# SCH-FlipperZero-FlipperPhone-V0_1.net
KiCad netlist of a schematic drawn in EasyEDA
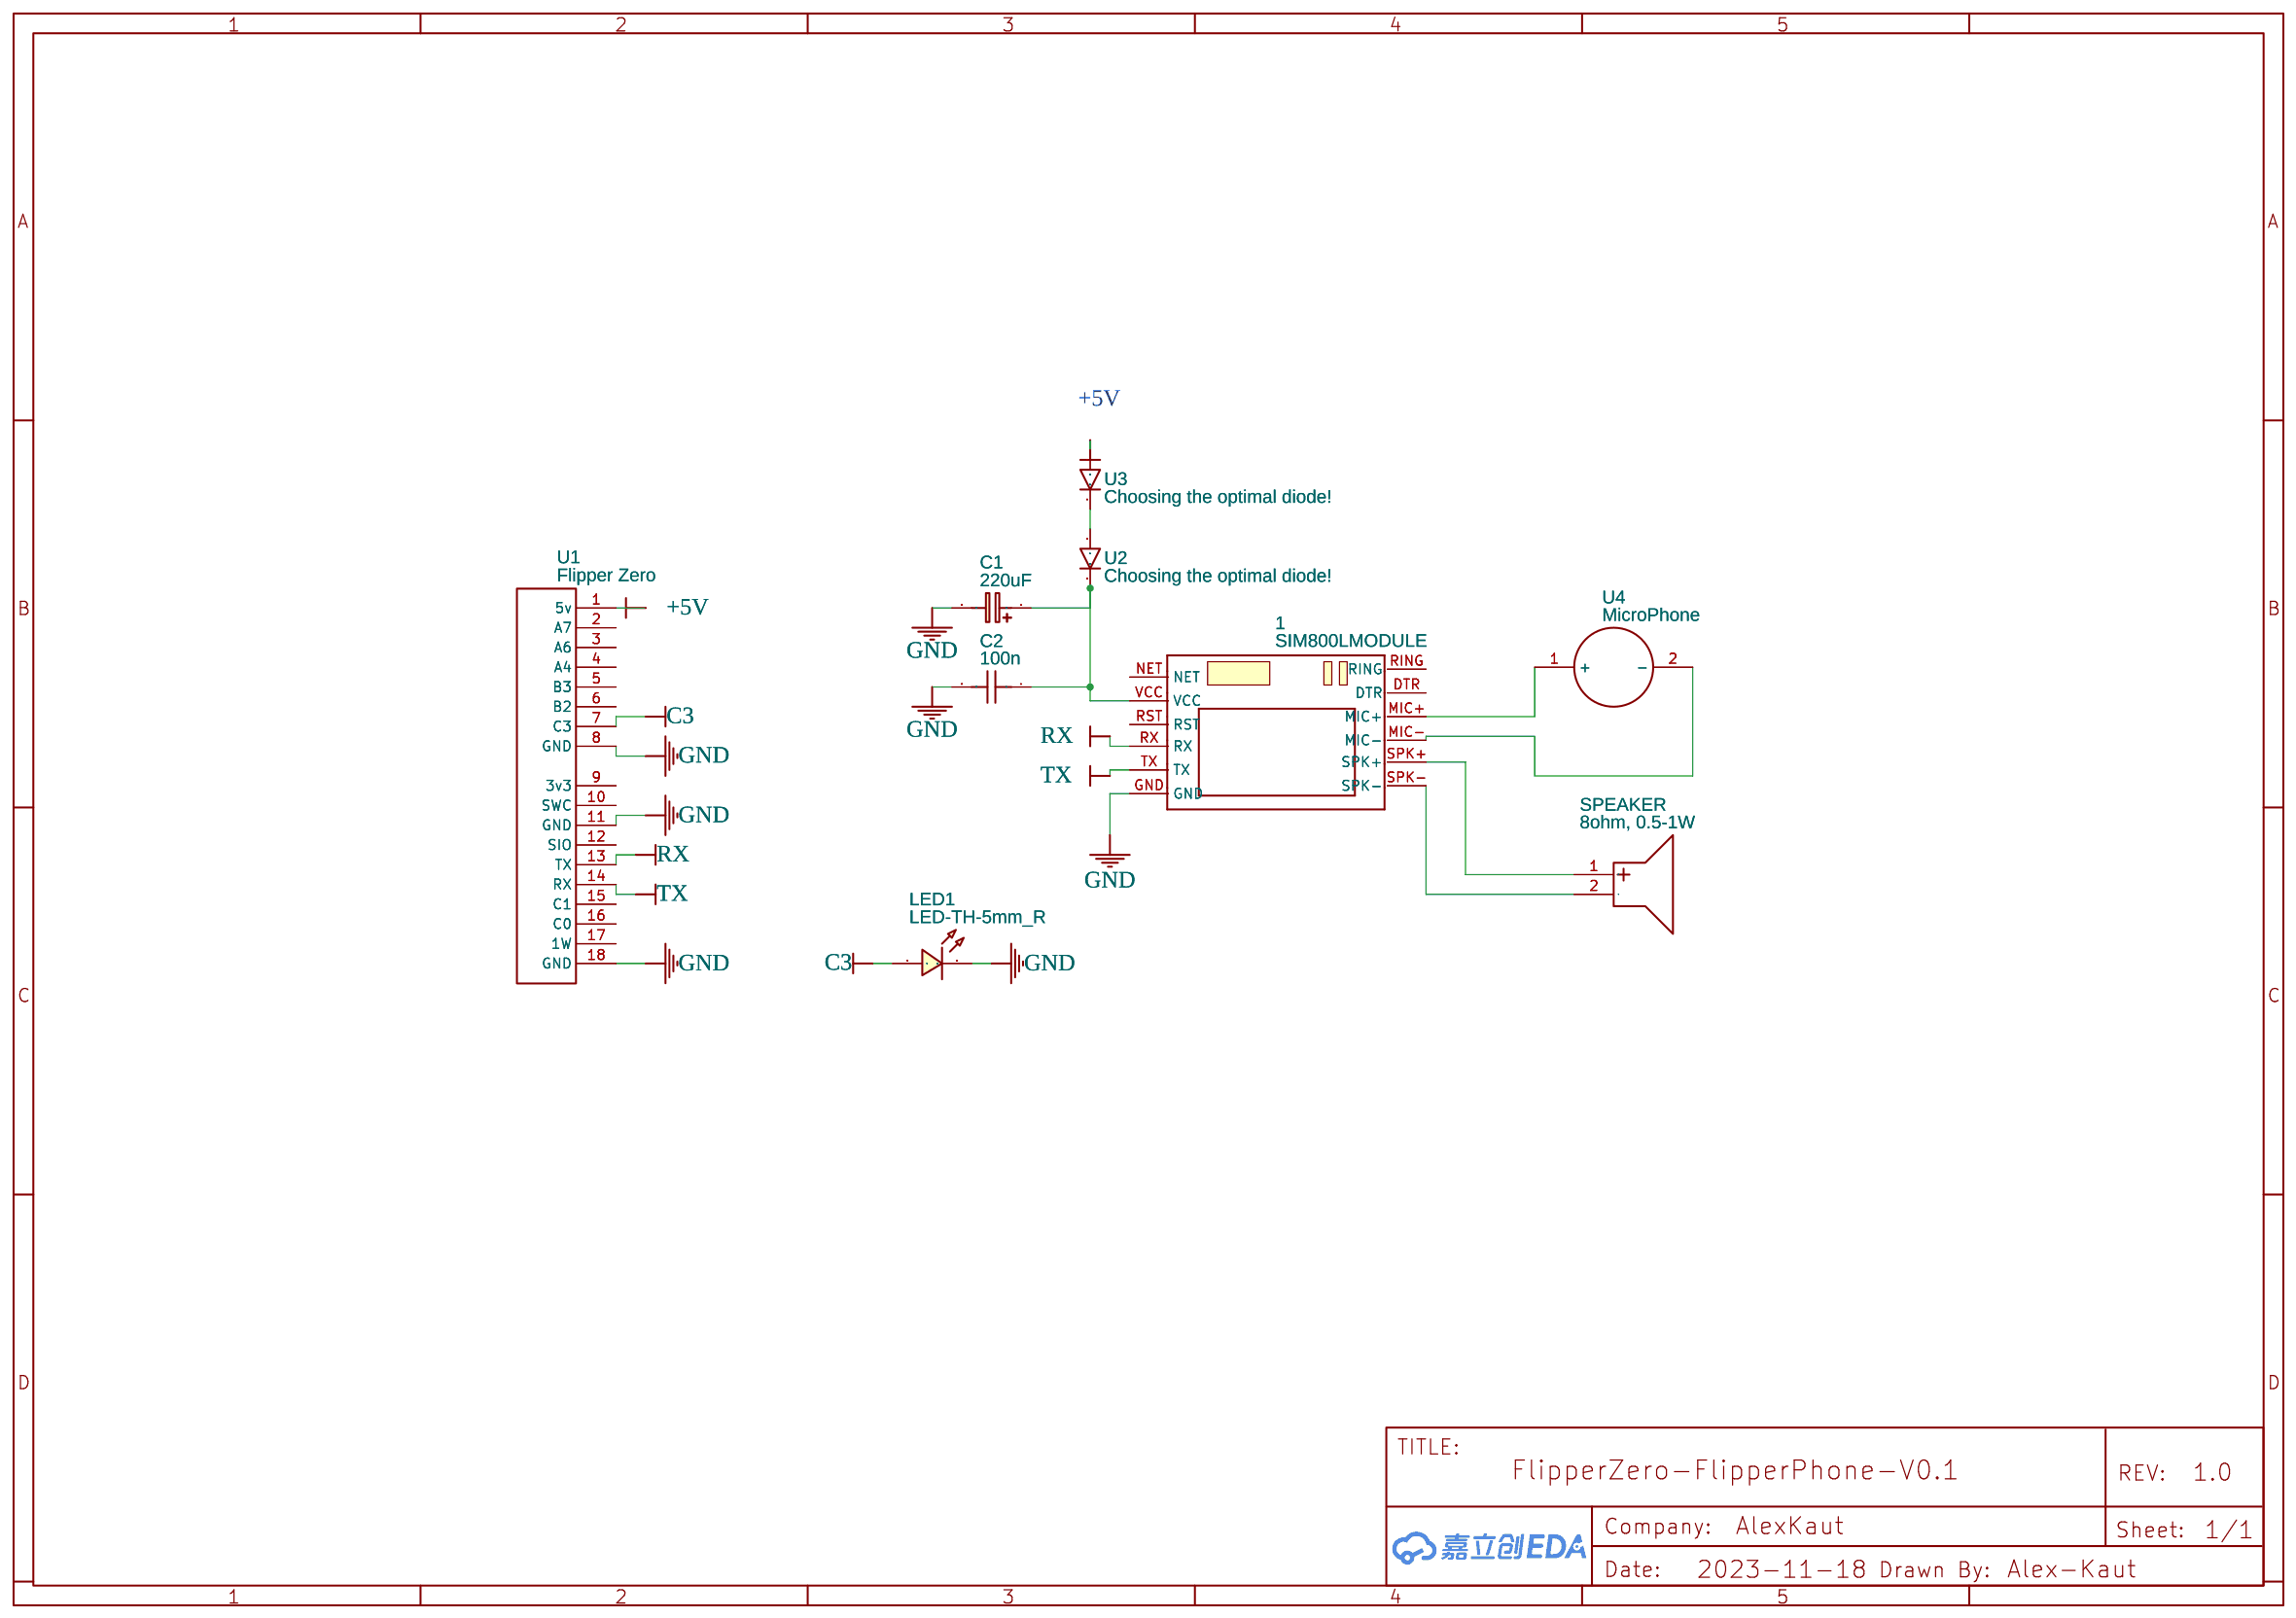
[diagram p0: schematic sheet]

(export (version "E")
  (design (tool "Eeschema 10.0.6"))
  (components
    (comp (ref "1") (value "SIM800LMODULE") (libsource (lib "") (part "SIM800LMODULE")))
    (comp (ref "C1") (value "220uF") (libsource (lib "") (part "CE_TH_D6.3×F2.5_EU")))
    (comp (ref "C2") (value "100n") (libsource (lib "") (part "C_RAD-0.2_US")))
    (comp (ref "LED1")
      (value "LED-TH-5mm_R")
      (fields
        (field (name "BOM_Manufacturer Part") "333-2SURD/S530-A3")
        (field (name "BOM_Supplier Part") "C87271")
      )
      (libsource (lib "") (part "LED-TH-5mm_R"))
    )
    (comp (ref "SPEAKER")
      (value "8ohm, 0.5-1W")
      (fields
        (field (name "BOM_Manufacturer Part") "BL-PBZ12065C2705YA")
        (field (name "BOM_Supplier Part") "C249440")
      )
      (libsource (lib "") (part "SPEAKER-30mm-8ohm-0.5w-TH"))
    )
    (comp (ref "U1") (value "Flipper Zero") (libsource (lib "") (part "Flipper Zero")))
    (comp (ref "U2") (value "Choosing the optimal diode!") (libsource (lib "") (part "1N4007A")))
    (comp (ref "U3") (value "Choosing the optimal diode!") (libsource (lib "") (part "1N4007A")))
    (comp (ref "U4") (value "MicroPhone") (libsource (lib "") (part "MicroPhone")))
  )
  (nets
    (net (code "1") (name "+5V") (class "Default")
      (node (ref "U1") (pin "1") (pinfunction "5v_1") (pintype "unspecified"))
      (node (ref "U3") (pin "1") (pinfunction "1_1") (pintype "unspecified"))
    )
    (net (code "2") (name "C3") (class "Default")
      (node (ref "LED1") (pin "1") (pinfunction "1_1") (pintype "unspecified"))
      (node (ref "U1") (pin "7") (pinfunction "C3_7") (pintype "unspecified"))
    )
    (net (code "3") (name "GND") (class "Default")
      (node (ref "1") (pin "GND") (pinfunction "GND_GND") (pintype "bidirectional"))
      (node (ref "C1") (pin "2") (pinfunction "2_2") (pintype "unspecified"))
      (node (ref "C2") (pin "2") (pinfunction "2_2") (pintype "unspecified"))
      (node (ref "LED1") (pin "2") (pinfunction "2_2") (pintype "unspecified"))
      (node (ref "U1") (pin "11") (pinfunction "GND_11") (pintype "unspecified"))
      (node (ref "U1") (pin "18") (pinfunction "GND_18") (pintype "unspecified"))
      (node (ref "U1") (pin "8") (pinfunction "GND_8") (pintype "unspecified"))
    )
    (net (code "4") (name "Net-(1-PadVCC)") (class "Default")
      (node (ref "1") (pin "VCC") (pinfunction "VCC_VCC") (pintype "bidirectional"))
      (node (ref "C1") (pin "1") (pinfunction "1_1") (pintype "unspecified"))
      (node (ref "C2") (pin "1") (pinfunction "1_1") (pintype "unspecified"))
      (node (ref "U2") (pin "2") (pinfunction "2_2") (pintype "unspecified"))
    )
    (net (code "5") (name "Net-(SPEAKER-+)") (class "Default")
      (node (ref "1") (pin "SPK+") (pinfunction "SPK+_SPK+") (pintype "bidirectional"))
      (node (ref "SPEAKER") (pin "1") (pinfunction "+_1") (pintype "unspecified"))
    )
    (net (code "6") (name "Net-(SPEAKER--)") (class "Default")
      (node (ref "1") (pin "SPK-") (pinfunction "SPK-_SPK-") (pintype "bidirectional"))
      (node (ref "SPEAKER") (pin "2") (pinfunction "-_2") (pintype "unspecified"))
    )
    (net (code "7") (name "Net-(U2-Pad1)") (class "Default")
      (node (ref "U2") (pin "1") (pinfunction "1_1") (pintype "unspecified"))
      (node (ref "U3") (pin "2") (pinfunction "2_2") (pintype "unspecified"))
    )
    (net (code "8") (name "Net-(U4-+)") (class "Default")
      (node (ref "1") (pin "MIC+") (pinfunction "MIC+_MIC+") (pintype "bidirectional"))
      (node (ref "U4") (pin "1") (pinfunction "+_1") (pintype "unspecified"))
    )
    (net (code "9") (name "Net-(U4--)") (class "Default")
      (node (ref "1") (pin "MIC-") (pinfunction "MIC-_MIC-") (pintype "bidirectional"))
      (node (ref "U4") (pin "2") (pinfunction "-_2") (pintype "unspecified"))
    )
    (net (code "10") (name "RX") (class "Default")
      (node (ref "1") (pin "RX") (pinfunction "RX_RX") (pintype "bidirectional"))
      (node (ref "U1") (pin "13") (pinfunction "TX_13") (pintype "unspecified"))
    )
    (net (code "11") (name "TX") (class "Default")
      (node (ref "1") (pin "TX") (pinfunction "TX_TX") (pintype "bidirectional"))
      (node (ref "U1") (pin "14") (pinfunction "RX_14") (pintype "unspecified"))
    )
    (net (code "12") (name "unconnected-(1-PadDTR)") (class "Default")
      (node (ref "1") (pin "DTR") (pinfunction "DTR_DTR") (pintype "bidirectional"))
    )
    (net (code "13") (name "unconnected-(1-PadNET)") (class "Default")
      (node (ref "1") (pin "NET") (pinfunction "NET_NET") (pintype "bidirectional"))
    )
    (net (code "14") (name "unconnected-(1-PadRING)") (class "Default")
      (node (ref "1") (pin "RING") (pinfunction "RING_RING") (pintype "bidirectional"))
    )
    (net (code "15") (name "unconnected-(1-PadRST)") (class "Default")
      (node (ref "1") (pin "RST") (pinfunction "RST_RST") (pintype "bidirectional"))
    )
    (net (code "16") (name "unconnected-(U1-1W-Pad17)") (class "Default")
      (node (ref "U1") (pin "17") (pinfunction "1W_17") (pintype "unspecified"))
    )
    (net (code "17") (name "unconnected-(U1-3v3-Pad9)") (class "Default")
      (node (ref "U1") (pin "9") (pinfunction "3v3_9") (pintype "unspecified"))
    )
    (net (code "18") (name "unconnected-(U1-A4-Pad4)") (class "Default")
      (node (ref "U1") (pin "4") (pinfunction "A4_4") (pintype "unspecified"))
    )
    (net (code "19") (name "unconnected-(U1-A6-Pad3)") (class "Default")
      (node (ref "U1") (pin "3") (pinfunction "A6_3") (pintype "unspecified"))
    )
    (net (code "20") (name "unconnected-(U1-A7-Pad2)") (class "Default")
      (node (ref "U1") (pin "2") (pinfunction "A7_2") (pintype "unspecified"))
    )
    (net (code "21") (name "unconnected-(U1-B2-Pad6)") (class "Default")
      (node (ref "U1") (pin "6") (pinfunction "B2_6") (pintype "unspecified"))
    )
    (net (code "22") (name "unconnected-(U1-B3-Pad5)") (class "Default")
      (node (ref "U1") (pin "5") (pinfunction "B3_5") (pintype "unspecified"))
    )
    (net (code "23") (name "unconnected-(U1-C0-Pad16)") (class "Default")
      (node (ref "U1") (pin "16") (pinfunction "C0_16") (pintype "unspecified"))
    )
    (net (code "24") (name "unconnected-(U1-C1-Pad15)") (class "Default")
      (node (ref "U1") (pin "15") (pinfunction "C1_15") (pintype "unspecified"))
    )
    (net (code "25") (name "unconnected-(U1-SIO-Pad12)") (class "Default")
      (node (ref "U1") (pin "12") (pinfunction "SIO_12") (pintype "unspecified"))
    )
    (net (code "26") (name "unconnected-(U1-SWC-Pad10)") (class "Default")
      (node (ref "U1") (pin "10") (pinfunction "SWC_10") (pintype "unspecified"))
    )
  )
)
